# CO_Monitor.net
KiCad netlist of a schematic drawn in EAGLE
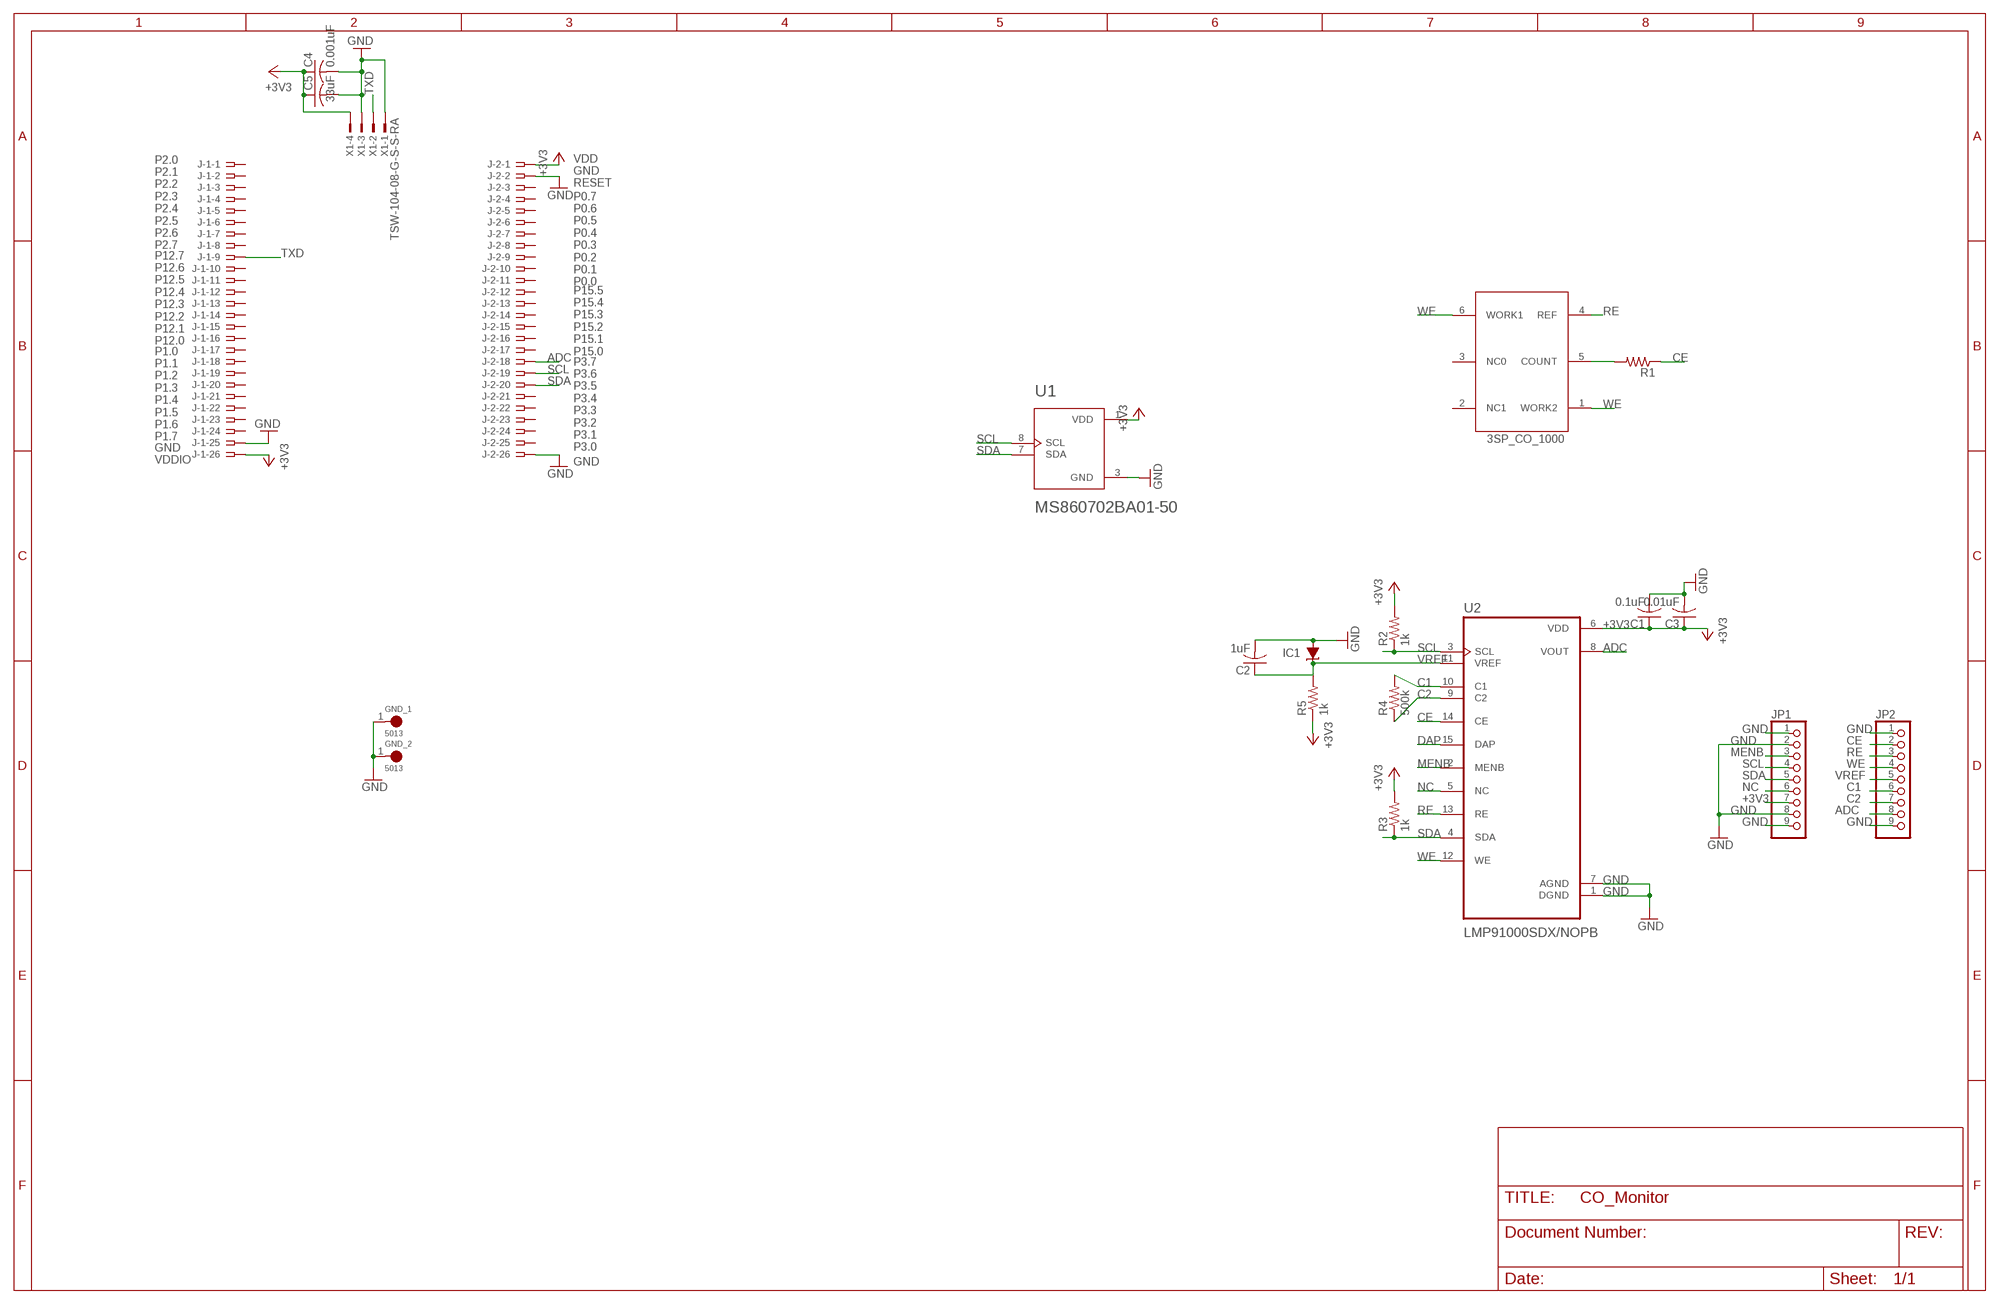
[diagram p0: schematic, sheet 1]

(export (version "E")
  (design (tool "Eeschema 10.0.6"))
  (components
    (comp (ref "C1")
      (value "0.1uF")
      (footprint "eagle-import:C050-025X075")
      (libsource (lib "eagle-import") (part "C-US050-025X075"))
    )
    (comp (ref "C2")
      (value "1uF")
      (footprint "eagle-import:C050-025X075")
      (libsource (lib "eagle-import") (part "C-US050-025X075"))
    )
    (comp (ref "C3")
      (value "0.01uF")
      (footprint "eagle-import:C050-025X075")
      (libsource (lib "eagle-import") (part "C-US050-025X075"))
    )
    (comp (ref "C4")
      (value "0.001uF")
      (footprint "eagle-import:C050-025X075")
      (libsource (lib "eagle-import") (part "C-US050-025X075"))
    )
    (comp (ref "C5")
      (value "33uF")
      (footprint "eagle-import:C050-025X075")
      (libsource (lib "eagle-import") (part "C-US050-025X075"))
    )
    (comp (ref "GND_1")
      (value "5013")
      (footprint "eagle-import:TESTPOINT_5013")
      (fields (field (name "MF") "Keystone Electronics"))
      (libsource (lib "eagle-import") (part "5013"))
    )
    (comp (ref "GND_2")
      (value "5013")
      (footprint "eagle-import:TESTPOINT_5013")
      (fields (field (name "MF") "Keystone Electronics"))
      (libsource (lib "eagle-import") (part "5013"))
    )
    (comp (ref "IC1")
      (value "LM4041D12LP")
      (footprint "eagle-import:LP_O-PBCY-W3")
      (fields (field (name "MPN") "LM4041D12ILP"))
      (libsource (lib "eagle-import") (part "LM4041LPD12"))
    )
    (comp (ref "J-1")
      (value "SSW-126-02-G-S")
      (footprint "eagle-import:SSW-126-02-G-S")
      (fields (field (name "MF") "Samtec Inc."))
      (libsource (lib "eagle-import") (part "SSW-126-02-G-S"))
    )
    (comp (ref "J-2")
      (value "SSW-126-02-G-S")
      (footprint "eagle-import:SSW-126-02-G-S")
      (fields (field (name "MF") "Samtec Inc."))
      (libsource (lib "eagle-import") (part "SSW-126-02-G-S"))
    )
    (comp (ref "JP1")
      (value "PINHD-1X9")
      (footprint "eagle-import:1X09")
      (libsource (lib "eagle-import") (part "PINHD-1X9"))
    )
    (comp (ref "JP2")
      (value "PINHD-1X9")
      (footprint "eagle-import:1X09")
      (libsource (lib "eagle-import") (part "PINHD-1X9"))
    )
    (comp (ref "R1")
      (value "50")
      (footprint "eagle-import:0207_10")
      (libsource (lib "eagle-import") (part "R-US_0207/10"))
    )
    (comp (ref "R2")
      (value "1k")
      (footprint "eagle-import:0207_10")
      (libsource (lib "eagle-import") (part "R-US_0207/10"))
    )
    (comp (ref "R3")
      (value "1k")
      (footprint "eagle-import:0207_10")
      (libsource (lib "eagle-import") (part "R-US_0207/10"))
    )
    (comp (ref "R4")
      (value "500k")
      (footprint "eagle-import:0207_10")
      (libsource (lib "eagle-import") (part "R-US_0207/10"))
    )
    (comp (ref "R5")
      (value "1k")
      (footprint "eagle-import:0207_10")
      (libsource (lib "eagle-import") (part "R-US_0207/10"))
    )
    (comp (ref "U$1")
      (value "3SP_CO_1000")
      (footprint "eagle-import:3SP_CO_1000")
      (libsource (lib "eagle-import") (part "3SP_CO_1000"))
    )
    (comp (ref "U1")
      (value "MS860702BA01-50")
      (footprint "eagle-import:TE_MS860702BA01-50")
      (fields (field (name "MF") "TE Connectivity"))
      (libsource (lib "eagle-import") (part "MS860702BA01-50"))
    )
    (comp (ref "U2")
      (value "LMP91000SDX/NOPB")
      (footprint "eagle-import:SON50P400X400X80-15N")
      (fields (field (name "MF") "Texas Instruments"))
      (libsource (lib "eagle-import") (part "LMP91000SDX/NOPB"))
    )
    (comp (ref "X1")
      (value "TSW-104-08-G-S-S-RA")
      (footprint "eagle-import:TSW-104-08-G-S-RA")
      (fields (field (name "MF") "Samtec Inc.") (field (name "MPN") "TSW-104-08-G-S-RA"))
      (libsource (lib "eagle-import") (part "TSW-104--G-S-S-RA08"))
    )
  )
  (nets
    (net (code "1") (name "+3V3") (class "Default")
      (node (ref "C1") (pin "1") (pinfunction "1_1") (pintype "passive"))
      (node (ref "C3") (pin "1") (pinfunction "1_1") (pintype "passive"))
      (node (ref "C4") (pin "1") (pinfunction "1_1") (pintype "passive"))
      (node (ref "C5") (pin "1") (pinfunction "1_1") (pintype "passive"))
      (node (ref "J-1") (pin "26") (pinfunction "1_26") (pintype "passive"))
      (node (ref "J-2") (pin "1") (pinfunction "1_1") (pintype "passive"))
      (node (ref "JP1") (pin "7") (pinfunction "7_7") (pintype "passive"))
      (node (ref "R2") (pin "2") (pinfunction "2_2") (pintype "passive"))
      (node (ref "R3") (pin "2") (pinfunction "2_2") (pintype "passive"))
      (node (ref "R5") (pin "1") (pinfunction "1_1") (pintype "passive"))
      (node (ref "U1") (pin "1") (pinfunction "VDD_1") (pintype "power_in"))
      (node (ref "U2") (pin "6") (pinfunction "VDD_6") (pintype "power_in"))
      (node (ref "X1") (pin "4") (pinfunction "1_4") (pintype "passive"))
    )
    (net (code "2") (name "/ADC") (class "Default")
      (node (ref "J-2") (pin "18") (pinfunction "1_18") (pintype "passive"))
      (node (ref "JP2") (pin "8") (pinfunction "8_8") (pintype "passive"))
      (node (ref "U2") (pin "8") (pinfunction "VOUT_8") (pintype "output"))
    )
    (net (code "3") (name "/C1") (class "Default")
      (node (ref "JP2") (pin "6") (pinfunction "6_6") (pintype "passive"))
      (node (ref "R4") (pin "2") (pinfunction "2_2") (pintype "passive"))
      (node (ref "U2") (pin "10") (pinfunction "C1_10") (pintype "bidirectional"))
    )
    (net (code "4") (name "/C2") (class "Default")
      (node (ref "JP2") (pin "7") (pinfunction "7_7") (pintype "passive"))
      (node (ref "R4") (pin "1") (pinfunction "1_1") (pintype "passive"))
      (node (ref "U2") (pin "9") (pinfunction "C2_9") (pintype "bidirectional"))
    )
    (net (code "5") (name "/CE") (class "Default")
      (node (ref "JP2") (pin "2") (pinfunction "2_2") (pintype "passive"))
      (node (ref "R1") (pin "1") (pinfunction "1_1") (pintype "passive"))
      (node (ref "U2") (pin "14") (pinfunction "CE_14") (pintype "bidirectional"))
    )
    (net (code "6") (name "/DAP") (class "Default")
      (node (ref "U2") (pin "15") (pinfunction "DAP_15") (pintype "bidirectional"))
    )
    (net (code "7") (name "/MENB") (class "Default")
      (node (ref "JP1") (pin "3") (pinfunction "3_3") (pintype "passive"))
      (node (ref "U2") (pin "2") (pinfunction "MENB_2") (pintype "bidirectional"))
    )
    (net (code "8") (name "/NC") (class "Default")
      (node (ref "JP1") (pin "6") (pinfunction "6_6") (pintype "passive"))
      (node (ref "U2") (pin "5") (pinfunction "NC_5") (pintype "bidirectional"))
    )
    (net (code "9") (name "/RE") (class "Default")
      (node (ref "JP2") (pin "3") (pinfunction "3_3") (pintype "passive"))
      (node (ref "U$1") (pin "4") (pinfunction "REF_4") (pintype "bidirectional"))
      (node (ref "U2") (pin "13") (pinfunction "RE_13") (pintype "bidirectional"))
    )
    (net (code "10") (name "/SCL") (class "Default")
      (node (ref "J-2") (pin "19") (pinfunction "1_19") (pintype "passive"))
      (node (ref "JP1") (pin "4") (pinfunction "4_4") (pintype "passive"))
      (node (ref "R2") (pin "1") (pinfunction "1_1") (pintype "passive"))
      (node (ref "U1") (pin "8") (pinfunction "SCL_8") (pintype "input"))
      (node (ref "U2") (pin "3") (pinfunction "SCL_3") (pintype "input"))
    )
    (net (code "11") (name "/SDA") (class "Default")
      (node (ref "J-2") (pin "20") (pinfunction "1_20") (pintype "passive"))
      (node (ref "JP1") (pin "5") (pinfunction "5_5") (pintype "passive"))
      (node (ref "R3") (pin "1") (pinfunction "1_1") (pintype "passive"))
      (node (ref "U1") (pin "7") (pinfunction "SDA_7") (pintype "bidirectional"))
      (node (ref "U2") (pin "4") (pinfunction "SDA_4") (pintype "bidirectional"))
    )
    (net (code "12") (name "/TXD") (class "Default")
      (node (ref "J-1") (pin "9") (pinfunction "1_9") (pintype "passive"))
      (node (ref "X1") (pin "2") (pinfunction "1_2") (pintype "passive"))
    )
    (net (code "13") (name "/VREF") (class "Default")
      (node (ref "C2") (pin "1") (pinfunction "1_1") (pintype "passive"))
      (node (ref "IC1") (pin "2") (pinfunction "C_2") (pintype "passive"))
      (node (ref "JP2") (pin "5") (pinfunction "5_5") (pintype "passive"))
      (node (ref "R5") (pin "2") (pinfunction "2_2") (pintype "passive"))
      (node (ref "U2") (pin "11") (pinfunction "VREF_11") (pintype "input"))
    )
    (net (code "14") (name "/WE") (class "Default")
      (node (ref "JP2") (pin "4") (pinfunction "4_4") (pintype "passive"))
      (node (ref "U$1") (pin "1") (pinfunction "WORK2_1") (pintype "bidirectional"))
      (node (ref "U$1") (pin "6") (pinfunction "WORK1_6") (pintype "bidirectional"))
      (node (ref "U2") (pin "12") (pinfunction "WE_12") (pintype "bidirectional"))
    )
    (net (code "15") (name "GND") (class "Default")
      (node (ref "C1") (pin "2") (pinfunction "2_2") (pintype "passive"))
      (node (ref "C2") (pin "2") (pinfunction "2_2") (pintype "passive"))
      (node (ref "C3") (pin "2") (pinfunction "2_2") (pintype "passive"))
      (node (ref "C4") (pin "2") (pinfunction "2_2") (pintype "passive"))
      (node (ref "C5") (pin "2") (pinfunction "2_2") (pintype "passive"))
      (node (ref "GND_1") (pin "1") (pinfunction "TP_1") (pintype "passive"))
      (node (ref "GND_2") (pin "1") (pinfunction "TP_1") (pintype "passive"))
      (node (ref "IC1") (pin "3") (pinfunction "A_3") (pintype "passive"))
      (node (ref "J-1") (pin "25") (pinfunction "1_25") (pintype "passive"))
      (node (ref "J-2") (pin "2") (pinfunction "1_2") (pintype "passive"))
      (node (ref "J-2") (pin "26") (pinfunction "1_26") (pintype "passive"))
      (node (ref "JP1") (pin "1") (pinfunction "1_1") (pintype "passive"))
      (node (ref "JP1") (pin "2") (pinfunction "2_2") (pintype "passive"))
      (node (ref "JP1") (pin "8") (pinfunction "8_8") (pintype "passive"))
      (node (ref "JP1") (pin "9") (pinfunction "9_9") (pintype "passive"))
      (node (ref "JP2") (pin "1") (pinfunction "1_1") (pintype "passive"))
      (node (ref "JP2") (pin "9") (pinfunction "9_9") (pintype "passive"))
      (node (ref "U1") (pin "3") (pinfunction "GND_3") (pintype "power_in"))
      (node (ref "U2") (pin "1") (pinfunction "DGND_1") (pintype "power_in"))
      (node (ref "U2") (pin "7") (pinfunction "AGND_7") (pintype "power_in"))
      (node (ref "X1") (pin "1") (pinfunction "1_1") (pintype "passive"))
      (node (ref "X1") (pin "3") (pinfunction "1_3") (pintype "passive"))
    )
    (net (code "16") (name "Net-(U$1-COUNT)") (class "Default")
      (node (ref "R1") (pin "2") (pinfunction "2_2") (pintype "passive"))
      (node (ref "U$1") (pin "5") (pinfunction "COUNT_5") (pintype "bidirectional"))
    )
    (net (code "17") (name "unconnected-(J-1-Pad1)") (class "Default")
      (node (ref "J-1") (pin "1") (pinfunction "1_1") (pintype "passive"))
    )
    (net (code "18") (name "unconnected-(J-1B-1-Pad10)") (class "Default")
      (node (ref "J-1") (pin "10") (pinfunction "1_10") (pintype "passive"))
    )
    (net (code "19") (name "unconnected-(J-1C-1-Pad11)") (class "Default")
      (node (ref "J-1") (pin "11") (pinfunction "1_11") (pintype "passive"))
    )
    (net (code "20") (name "unconnected-(J-1D-1-Pad12)") (class "Default")
      (node (ref "J-1") (pin "12") (pinfunction "1_12") (pintype "passive"))
    )
    (net (code "21") (name "unconnected-(J-1E-1-Pad13)") (class "Default")
      (node (ref "J-1") (pin "13") (pinfunction "1_13") (pintype "passive"))
    )
    (net (code "22") (name "unconnected-(J-1F-1-Pad14)") (class "Default")
      (node (ref "J-1") (pin "14") (pinfunction "1_14") (pintype "passive"))
    )
    (net (code "23") (name "unconnected-(J-1G-1-Pad15)") (class "Default")
      (node (ref "J-1") (pin "15") (pinfunction "1_15") (pintype "passive"))
    )
    (net (code "24") (name "unconnected-(J-1H-1-Pad16)") (class "Default")
      (node (ref "J-1") (pin "16") (pinfunction "1_16") (pintype "passive"))
    )
    (net (code "25") (name "unconnected-(J-1I-1-Pad17)") (class "Default")
      (node (ref "J-1") (pin "17") (pinfunction "1_17") (pintype "passive"))
    )
    (net (code "26") (name "unconnected-(J-1J-1-Pad18)") (class "Default")
      (node (ref "J-1") (pin "18") (pinfunction "1_18") (pintype "passive"))
    )
    (net (code "27") (name "unconnected-(J-1K-1-Pad19)") (class "Default")
      (node (ref "J-1") (pin "19") (pinfunction "1_19") (pintype "passive"))
    )
    (net (code "28") (name "unconnected-(J-1L-1-Pad2)") (class "Default")
      (node (ref "J-1") (pin "2") (pinfunction "1_2") (pintype "passive"))
    )
    (net (code "29") (name "unconnected-(J-1M-1-Pad20)") (class "Default")
      (node (ref "J-1") (pin "20") (pinfunction "1_20") (pintype "passive"))
    )
    (net (code "30") (name "unconnected-(J-1N-1-Pad21)") (class "Default")
      (node (ref "J-1") (pin "21") (pinfunction "1_21") (pintype "passive"))
    )
    (net (code "31") (name "unconnected-(J-1O-1-Pad22)") (class "Default")
      (node (ref "J-1") (pin "22") (pinfunction "1_22") (pintype "passive"))
    )
    (net (code "32") (name "unconnected-(J-1P-1-Pad23)") (class "Default")
      (node (ref "J-1") (pin "23") (pinfunction "1_23") (pintype "passive"))
    )
    (net (code "33") (name "unconnected-(J-1Q-1-Pad24)") (class "Default")
      (node (ref "J-1") (pin "24") (pinfunction "1_24") (pintype "passive"))
    )
    (net (code "34") (name "unconnected-(J-1T-1-Pad3)") (class "Default")
      (node (ref "J-1") (pin "3") (pinfunction "1_3") (pintype "passive"))
    )
    (net (code "35") (name "unconnected-(J-1U-1-Pad4)") (class "Default")
      (node (ref "J-1") (pin "4") (pinfunction "1_4") (pintype "passive"))
    )
    (net (code "36") (name "unconnected-(J-1V-1-Pad5)") (class "Default")
      (node (ref "J-1") (pin "5") (pinfunction "1_5") (pintype "passive"))
    )
    (net (code "37") (name "unconnected-(J-1W-1-Pad6)") (class "Default")
      (node (ref "J-1") (pin "6") (pinfunction "1_6") (pintype "passive"))
    )
    (net (code "38") (name "unconnected-(J-1X-1-Pad7)") (class "Default")
      (node (ref "J-1") (pin "7") (pinfunction "1_7") (pintype "passive"))
    )
    (net (code "39") (name "unconnected-(J-1Y-1-Pad8)") (class "Default")
      (node (ref "J-1") (pin "8") (pinfunction "1_8") (pintype "passive"))
    )
    (net (code "40") (name "unconnected-(J-2B-1-Pad10)") (class "Default")
      (node (ref "J-2") (pin "10") (pinfunction "1_10") (pintype "passive"))
    )
    (net (code "41") (name "unconnected-(J-2C-1-Pad11)") (class "Default")
      (node (ref "J-2") (pin "11") (pinfunction "1_11") (pintype "passive"))
    )
    (net (code "42") (name "unconnected-(J-2D-1-Pad12)") (class "Default")
      (node (ref "J-2") (pin "12") (pinfunction "1_12") (pintype "passive"))
    )
    (net (code "43") (name "unconnected-(J-2E-1-Pad13)") (class "Default")
      (node (ref "J-2") (pin "13") (pinfunction "1_13") (pintype "passive"))
    )
    (net (code "44") (name "unconnected-(J-2F-1-Pad14)") (class "Default")
      (node (ref "J-2") (pin "14") (pinfunction "1_14") (pintype "passive"))
    )
    (net (code "45") (name "unconnected-(J-2G-1-Pad15)") (class "Default")
      (node (ref "J-2") (pin "15") (pinfunction "1_15") (pintype "passive"))
    )
    (net (code "46") (name "unconnected-(J-2H-1-Pad16)") (class "Default")
      (node (ref "J-2") (pin "16") (pinfunction "1_16") (pintype "passive"))
    )
    (net (code "47") (name "unconnected-(J-2I-1-Pad17)") (class "Default")
      (node (ref "J-2") (pin "17") (pinfunction "1_17") (pintype "passive"))
    )
    (net (code "48") (name "unconnected-(J-2N-1-Pad21)") (class "Default")
      (node (ref "J-2") (pin "21") (pinfunction "1_21") (pintype "passive"))
    )
    (net (code "49") (name "unconnected-(J-2O-1-Pad22)") (class "Default")
      (node (ref "J-2") (pin "22") (pinfunction "1_22") (pintype "passive"))
    )
    (net (code "50") (name "unconnected-(J-2P-1-Pad23)") (class "Default")
      (node (ref "J-2") (pin "23") (pinfunction "1_23") (pintype "passive"))
    )
    (net (code "51") (name "unconnected-(J-2Q-1-Pad24)") (class "Default")
      (node (ref "J-2") (pin "24") (pinfunction "1_24") (pintype "passive"))
    )
    (net (code "52") (name "unconnected-(J-2R-1-Pad25)") (class "Default")
      (node (ref "J-2") (pin "25") (pinfunction "1_25") (pintype "passive"))
    )
    (net (code "53") (name "unconnected-(J-2T-1-Pad3)") (class "Default")
      (node (ref "J-2") (pin "3") (pinfunction "1_3") (pintype "passive"))
    )
    (net (code "54") (name "unconnected-(J-2U-1-Pad4)") (class "Default")
      (node (ref "J-2") (pin "4") (pinfunction "1_4") (pintype "passive"))
    )
    (net (code "55") (name "unconnected-(J-2V-1-Pad5)") (class "Default")
      (node (ref "J-2") (pin "5") (pinfunction "1_5") (pintype "passive"))
    )
    (net (code "56") (name "unconnected-(J-2W-1-Pad6)") (class "Default")
      (node (ref "J-2") (pin "6") (pinfunction "1_6") (pintype "passive"))
    )
    (net (code "57") (name "unconnected-(J-2X-1-Pad7)") (class "Default")
      (node (ref "J-2") (pin "7") (pinfunction "1_7") (pintype "passive"))
    )
    (net (code "58") (name "unconnected-(J-2Y-1-Pad8)") (class "Default")
      (node (ref "J-2") (pin "8") (pinfunction "1_8") (pintype "passive"))
    )
    (net (code "59") (name "unconnected-(J-2Z-1-Pad9)") (class "Default")
      (node (ref "J-2") (pin "9") (pinfunction "1_9") (pintype "passive"))
    )
    (net (code "60") (name "unconnected-(U$1-NC0-Pad3)") (class "Default")
      (node (ref "U$1") (pin "3") (pinfunction "NC0_3") (pintype "bidirectional"))
    )
    (net (code "61") (name "unconnected-(U$1-NC1-Pad2)") (class "Default")
      (node (ref "U$1") (pin "2") (pinfunction "NC1_2") (pintype "bidirectional"))
    )
  )
)
